# HoverPuck.net
KiCad netlist of a schematic drawn in EAGLE
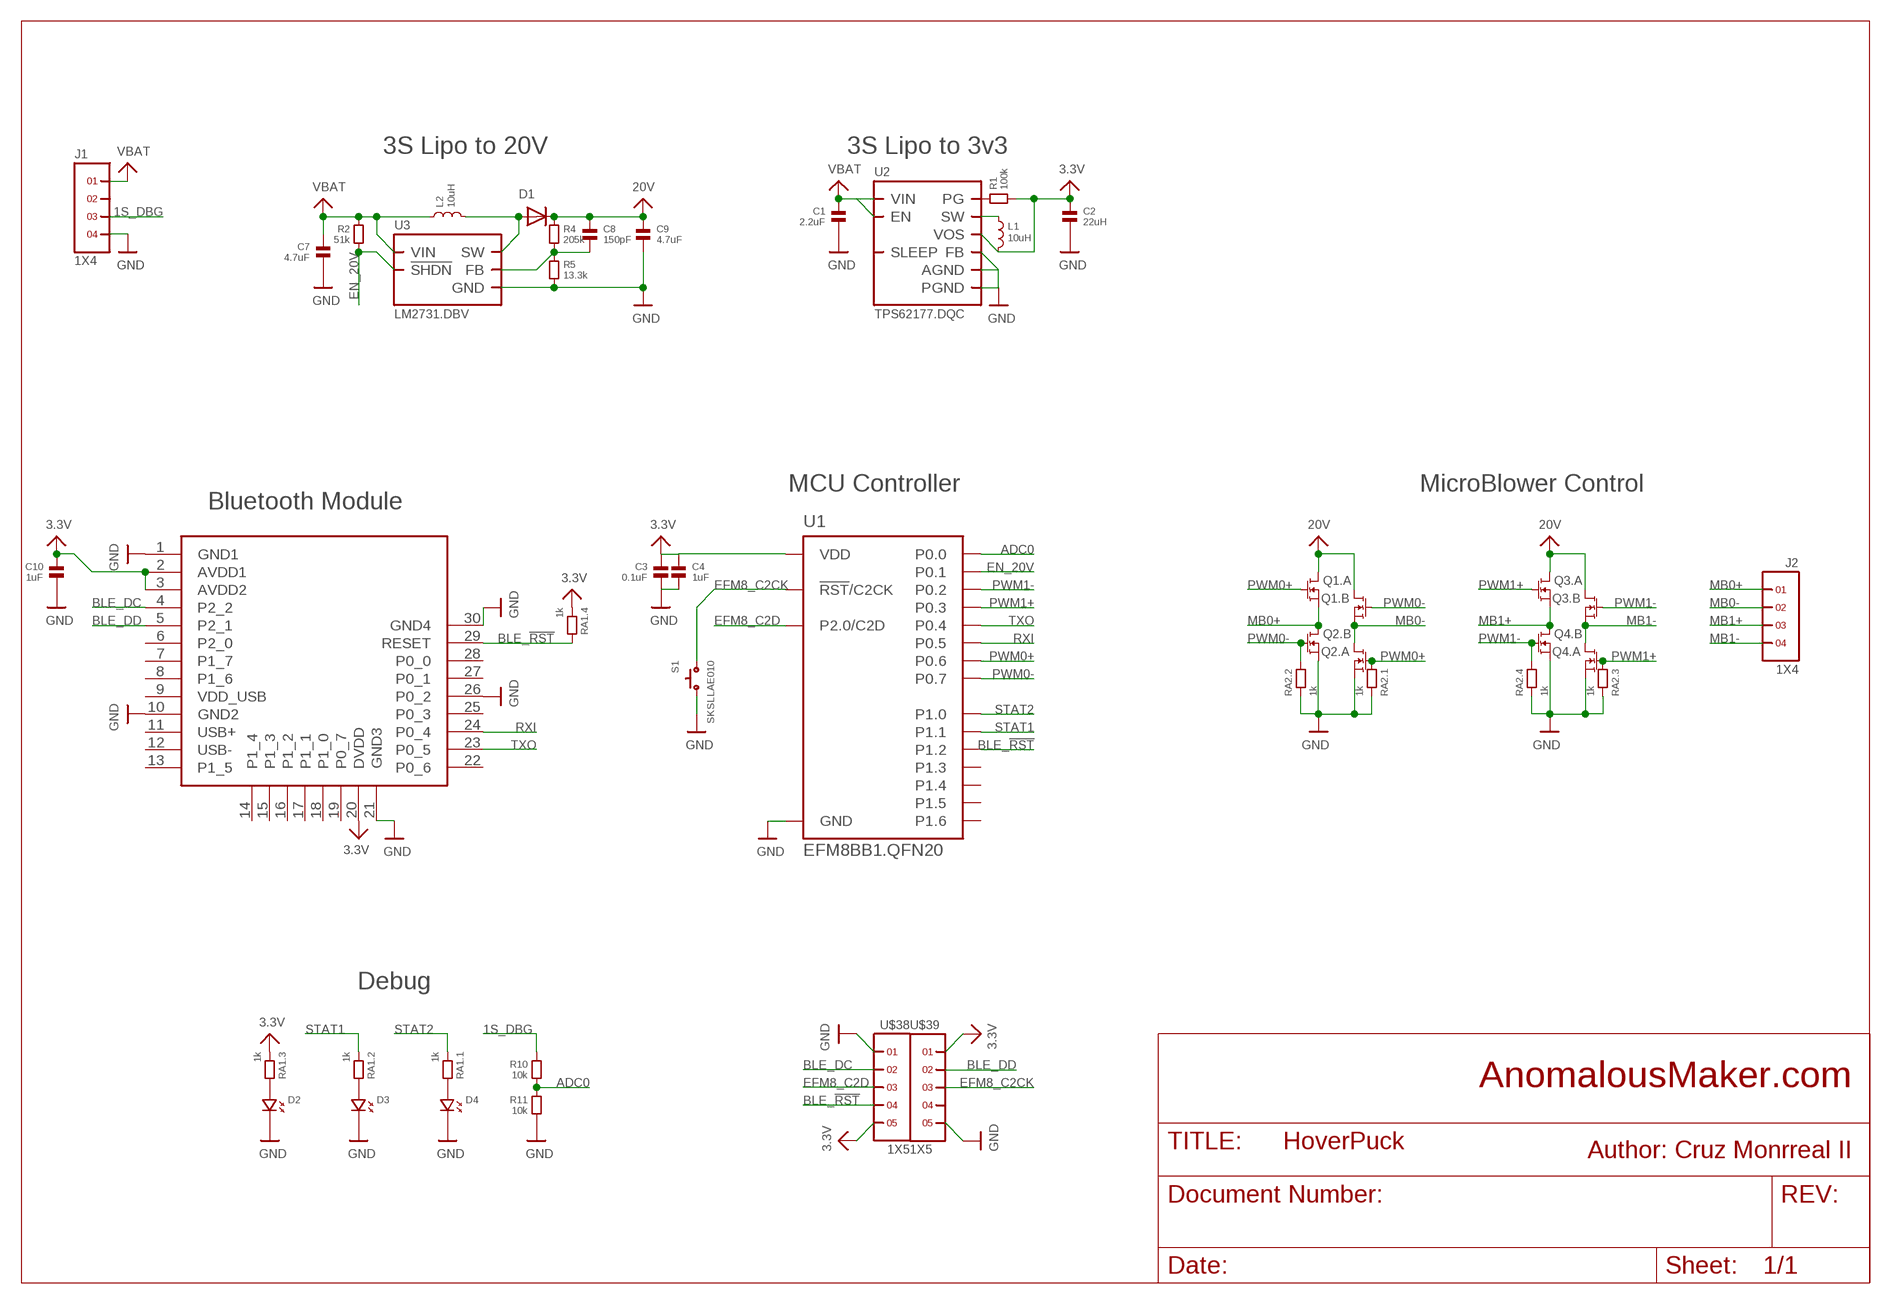
[diagram p0: schematic, sheet 1]

(export (version "E")
  (design (tool "Eeschema 10.0.6"))
  (components
    (comp (ref "C1")
      (value "2.2uF")
      (footprint "eagle-import:0603")
      (libsource (lib "eagle-import") (part "CAPACITOR.0603"))
    )
    (comp (ref "C2")
      (value "22uH")
      (footprint "eagle-import:0805")
      (libsource (lib "eagle-import") (part "CAPACITOR.0805"))
    )
    (comp (ref "C3")
      (value "0.1uF")
      (footprint "eagle-import:0603")
      (libsource (lib "eagle-import") (part "CAPACITOR.0603"))
    )
    (comp (ref "C4")
      (value "1uF")
      (footprint "eagle-import:0603")
      (libsource (lib "eagle-import") (part "CAPACITOR.0603"))
    )
    (comp (ref "C7")
      (value "4.7uF")
      (footprint "eagle-import:0805")
      (libsource (lib "eagle-import") (part "CAPACITOR.0805"))
    )
    (comp (ref "C8")
      (value "150pF")
      (footprint "eagle-import:0603")
      (libsource (lib "eagle-import") (part "CAPACITOR.0603"))
    )
    (comp (ref "C9")
      (value "4.7uF")
      (footprint "eagle-import:0805")
      (libsource (lib "eagle-import") (part "CAPACITOR.0805"))
    )
    (comp (ref "C10")
      (value "1uF")
      (footprint "eagle-import:0603")
      (libsource (lib "eagle-import") (part "CAPACITOR.0603"))
    )
    (comp (ref "D1")
      (value "MBR0530T1G")
      (footprint "eagle-import:SOD-123")
      (libsource (lib "eagle-import") (part "DIODESOD-123"))
    )
    (comp (ref "D2")
      (value "LED.0603")
      (footprint "eagle-import:0603.LED")
      (libsource (lib "eagle-import") (part "LED.0603"))
    )
    (comp (ref "D3")
      (value "LED.0603")
      (footprint "eagle-import:0603.LED")
      (libsource (lib "eagle-import") (part "LED.0603"))
    )
    (comp (ref "D4")
      (value "LED.0603")
      (footprint "eagle-import:0603.LED")
      (libsource (lib "eagle-import") (part "LED.0603"))
    )
    (comp (ref "J1")
      (value "1X4")
      (footprint "eagle-import:1X4")
      (libsource (lib "eagle-import") (part "1X4"))
    )
    (comp (ref "J2")
      (value "1X4")
      (footprint "eagle-import:1X4")
      (libsource (lib "eagle-import") (part "1X4"))
    )
    (comp (ref "L1")
      (value "10uH")
      (footprint "eagle-import:LPS4018")
      (libsource (lib "eagle-import") (part "INDUCTOR.LPS4018"))
    )
    (comp (ref "L2")
      (value "10uH")
      (footprint "eagle-import:SRN6045")
      (libsource (lib "eagle-import") (part "INDUCTOR-SRN6045"))
    )
    (comp (ref "Q1")
      (value "FDMA")
      (footprint "eagle-import:MICROFET.2X2")
      (libsource (lib "eagle-import") (part "FDMA"))
    )
    (comp (ref "Q2")
      (value "FDMA")
      (footprint "eagle-import:MICROFET.2X2")
      (libsource (lib "eagle-import") (part "FDMA"))
    )
    (comp (ref "Q3")
      (value "FDMA")
      (footprint "eagle-import:MICROFET.2X2")
      (libsource (lib "eagle-import") (part "FDMA"))
    )
    (comp (ref "Q4")
      (value "FDMA")
      (footprint "eagle-import:MICROFET.2X2")
      (libsource (lib "eagle-import") (part "FDMA"))
    )
    (comp (ref "R1")
      (value "100k")
      (footprint "eagle-import:0603")
      (libsource (lib "eagle-import") (part "RESISTOR.0603"))
    )
    (comp (ref "R2")
      (value "51k")
      (footprint "eagle-import:0603")
      (libsource (lib "eagle-import") (part "RESISTOR.0603"))
    )
    (comp (ref "R4")
      (value "205k")
      (footprint "eagle-import:0603")
      (libsource (lib "eagle-import") (part "RESISTOR.0603"))
    )
    (comp (ref "R5")
      (value "13.3k")
      (footprint "eagle-import:0603")
      (libsource (lib "eagle-import") (part "RESISTOR.0603"))
    )
    (comp (ref "R10")
      (value "10k")
      (footprint "eagle-import:0603")
      (libsource (lib "eagle-import") (part "RESISTOR.0603"))
    )
    (comp (ref "R11")
      (value "10k")
      (footprint "eagle-import:0603")
      (libsource (lib "eagle-import") (part "RESISTOR.0603"))
    )
    (comp (ref "RA1")
      (value "1k")
      (footprint "eagle-import:0603.4.C")
      (libsource (lib "eagle-import") (part "RA-4.0603"))
    )
    (comp (ref "RA2")
      (value "1k")
      (footprint "eagle-import:0603.4.C")
      (libsource (lib "eagle-import") (part "RA-4.0603"))
    )
    (comp (ref "S1")
      (value "SKSLLAE010")
      (footprint "eagle-import:SKSLLAE010")
      (libsource (lib "eagle-import") (part "SKSLLAE010"))
    )
    (comp (ref "U$38")
      (value "1X5")
      (footprint "eagle-import:1X5")
      (libsource (lib "eagle-import") (part "1X5"))
    )
    (comp (ref "U$39")
      (value "1X5")
      (footprint "eagle-import:1X5")
      (libsource (lib "eagle-import") (part "1X5"))
    )
    (comp (ref "U1")
      (value "EFM8BB1.QFN20")
      (footprint "eagle-import:QFN20")
      (libsource (lib "eagle-import") (part "EFM8BB1.QFN20"))
    )
    (comp (ref "U2")
      (value "TPS62177.DQC")
      (footprint "eagle-import:DQC")
      (libsource (lib "eagle-import") (part "TPS62177.DQC"))
    )
    (comp (ref "U3")
      (value "LM2731.DBV")
      (footprint "eagle-import:DBV.5")
      (libsource (lib "eagle-import") (part "LM2731.DBV"))
    )
    (comp (ref "U4")
      (value "BLE112-A")
      (footprint "eagle-import:BLE112-A")
      (libsource (lib "eagle-import") (part "BLE112-A"))
    )
  )
  (nets
    (net (code "1") (name "/1S_DBG") (class "Default")
      (node (ref "J1") (pin "3") (pinfunction "3_3") (pintype "bidirectional"))
      (node (ref "R10") (pin "1") (pinfunction "1_1") (pintype "bidirectional"))
    )
    (net (code "2") (name "/ADC0") (class "Default")
      (node (ref "R10") (pin "2") (pinfunction "2_2") (pintype "bidirectional"))
      (node (ref "R11") (pin "1") (pinfunction "1_1") (pintype "bidirectional"))
      (node (ref "U1") (pin "2") (pinfunction "P0.0_2") (pintype "bidirectional"))
    )
    (net (code "3") (name "/BLE_DC") (class "Default")
      (node (ref "U$38") (pin "2") (pinfunction "2_2") (pintype "bidirectional"))
      (node (ref "U4") (pin "4") (pinfunction "P2_2_4") (pintype "bidirectional"))
    )
    (net (code "4") (name "/BLE_DD") (class "Default")
      (node (ref "U$39") (pin "2") (pinfunction "2_2") (pintype "bidirectional"))
      (node (ref "U4") (pin "5") (pinfunction "P2_1_5") (pintype "bidirectional"))
    )
    (net (code "5") (name "/BLE_~{RST}") (class "Default")
      (node (ref "RA1") (pin "8") (pinfunction "2_8") (pintype "bidirectional"))
      (node (ref "U$38") (pin "4") (pinfunction "4_4") (pintype "bidirectional"))
      (node (ref "U1") (pin "11") (pinfunction "P1.2_11") (pintype "bidirectional"))
      (node (ref "U4") (pin "29") (pinfunction "RESET_29") (pintype "bidirectional"))
    )
    (net (code "6") (name "/EFM8_C2CK") (class "Default")
      (node (ref "S1") (pin "1") (pinfunction "1_1") (pintype "bidirectional"))
      (node (ref "U$39") (pin "3") (pinfunction "3_3") (pintype "bidirectional"))
      (node (ref "U1") (pin "5") (pinfunction "~{RST}/C2CK_5") (pintype "input"))
    )
    (net (code "7") (name "/EFM8_C2D") (class "Default")
      (node (ref "U$38") (pin "3") (pinfunction "3_3") (pintype "bidirectional"))
      (node (ref "U1") (pin "6") (pinfunction "P2.0/C2D_6") (pintype "bidirectional"))
    )
    (net (code "8") (name "/EN_20V") (class "Default")
      (node (ref "R2") (pin "2") (pinfunction "2_2") (pintype "bidirectional"))
      (node (ref "U1") (pin "1") (pinfunction "P0.1_1") (pintype "bidirectional"))
      (node (ref "U3") (pin "4") (pinfunction "~{SHDN}_4") (pintype "bidirectional"))
    )
    (net (code "9") (name "/MB0+") (class "Default")
      (node (ref "J2") (pin "1") (pinfunction "1_1") (pintype "bidirectional"))
      (node (ref "Q1") (pin "1") (pinfunction "S_1") (pintype "bidirectional"))
      (node (ref "Q2") (pin "3") (pinfunction "D_3") (pintype "bidirectional"))
      (node (ref "Q2") (pin "PAD@2") (pinfunction "D_PAD@2") (pintype "bidirectional"))
    )
    (net (code "10") (name "/MB0-") (class "Default")
      (node (ref "J2") (pin "2") (pinfunction "2_2") (pintype "bidirectional"))
      (node (ref "Q1") (pin "4") (pinfunction "S_4") (pintype "bidirectional"))
      (node (ref "Q2") (pin "6") (pinfunction "D_6") (pintype "bidirectional"))
      (node (ref "Q2") (pin "PAD@1") (pinfunction "D_PAD@1") (pintype "bidirectional"))
    )
    (net (code "11") (name "/MB1+") (class "Default")
      (node (ref "J2") (pin "3") (pinfunction "3_3") (pintype "bidirectional"))
      (node (ref "Q3") (pin "1") (pinfunction "S_1") (pintype "bidirectional"))
      (node (ref "Q4") (pin "3") (pinfunction "D_3") (pintype "bidirectional"))
      (node (ref "Q4") (pin "PAD@2") (pinfunction "D_PAD@2") (pintype "bidirectional"))
    )
    (net (code "12") (name "/MB1-") (class "Default")
      (node (ref "J2") (pin "4") (pinfunction "4_4") (pintype "bidirectional"))
      (node (ref "Q3") (pin "4") (pinfunction "S_4") (pintype "bidirectional"))
      (node (ref "Q4") (pin "6") (pinfunction "D_6") (pintype "bidirectional"))
      (node (ref "Q4") (pin "PAD@1") (pinfunction "D_PAD@1") (pintype "bidirectional"))
    )
    (net (code "13") (name "/PWM0+") (class "Default")
      (node (ref "Q1") (pin "2") (pinfunction "G_2") (pintype "bidirectional"))
      (node (ref "Q2") (pin "2") (pinfunction "G_2") (pintype "bidirectional"))
      (node (ref "RA2") (pin "2") (pinfunction "2_2") (pintype "bidirectional"))
      (node (ref "U1") (pin "16") (pinfunction "P0.6_16") (pintype "bidirectional"))
    )
    (net (code "14") (name "/PWM0-") (class "Default")
      (node (ref "Q1") (pin "5") (pinfunction "G_5") (pintype "bidirectional"))
      (node (ref "Q2") (pin "5") (pinfunction "G_5") (pintype "bidirectional"))
      (node (ref "RA2") (pin "4") (pinfunction "2_4") (pintype "bidirectional"))
      (node (ref "U1") (pin "15") (pinfunction "P0.7_15") (pintype "bidirectional"))
    )
    (net (code "15") (name "/PWM1+") (class "Default")
      (node (ref "Q3") (pin "2") (pinfunction "G_2") (pintype "bidirectional"))
      (node (ref "Q4") (pin "2") (pinfunction "G_2") (pintype "bidirectional"))
      (node (ref "RA2") (pin "6") (pinfunction "2_6") (pintype "bidirectional"))
      (node (ref "U1") (pin "19") (pinfunction "P0.3_19") (pintype "bidirectional"))
    )
    (net (code "16") (name "/PWM1-") (class "Default")
      (node (ref "Q3") (pin "5") (pinfunction "G_5") (pintype "bidirectional"))
      (node (ref "Q4") (pin "5") (pinfunction "G_5") (pintype "bidirectional"))
      (node (ref "RA2") (pin "8") (pinfunction "2_8") (pintype "bidirectional"))
      (node (ref "U1") (pin "20") (pinfunction "P0.2_20") (pintype "bidirectional"))
    )
    (net (code "17") (name "/RXI") (class "Default")
      (node (ref "U1") (pin "17") (pinfunction "P0.5_17") (pintype "bidirectional"))
      (node (ref "U4") (pin "24") (pinfunction "P0_4_24") (pintype "bidirectional"))
    )
    (net (code "18") (name "/STAT1") (class "Default")
      (node (ref "RA1") (pin "3") (pinfunction "1_3") (pintype "bidirectional"))
      (node (ref "U1") (pin "13") (pinfunction "P1.1_13") (pintype "bidirectional"))
    )
    (net (code "19") (name "/STAT2") (class "Default")
      (node (ref "RA1") (pin "1") (pinfunction "1_1") (pintype "bidirectional"))
      (node (ref "U1") (pin "14") (pinfunction "P1.0_14") (pintype "bidirectional"))
    )
    (net (code "20") (name "/TXO") (class "Default")
      (node (ref "U1") (pin "18") (pinfunction "P0.4_18") (pintype "bidirectional"))
      (node (ref "U4") (pin "23") (pinfunction "P0_5_23") (pintype "bidirectional"))
    )
    (net (code "21") (name "3.3V") (class "Default")
      (node (ref "C10") (pin "1") (pinfunction "1_1") (pintype "bidirectional"))
      (node (ref "C2") (pin "1") (pinfunction "1_1") (pintype "bidirectional"))
      (node (ref "C3") (pin "1") (pinfunction "1_1") (pintype "bidirectional"))
      (node (ref "C4") (pin "1") (pinfunction "1_1") (pintype "bidirectional"))
      (node (ref "L1") (pin "2") (pinfunction "2_2") (pintype "passive"))
      (node (ref "R1") (pin "2") (pinfunction "2_2") (pintype "bidirectional"))
      (node (ref "RA1") (pin "5") (pinfunction "1_5") (pintype "bidirectional"))
      (node (ref "RA1") (pin "7") (pinfunction "1_7") (pintype "bidirectional"))
      (node (ref "U$38") (pin "5") (pinfunction "5_5") (pintype "bidirectional"))
      (node (ref "U$39") (pin "1") (pinfunction "1_1") (pintype "bidirectional"))
      (node (ref "U1") (pin "4") (pinfunction "VDD_4") (pintype "power_in"))
      (node (ref "U2") (pin "10") (pinfunction "VOS_10") (pintype "bidirectional"))
      (node (ref "U4") (pin "2") (pinfunction "AVDD1_2") (pintype "bidirectional"))
      (node (ref "U4") (pin "20") (pinfunction "DVDD_20") (pintype "bidirectional"))
      (node (ref "U4") (pin "3") (pinfunction "AVDD2_3") (pintype "bidirectional"))
    )
    (net (code "22") (name "20V") (class "Default")
      (node (ref "C8") (pin "1") (pinfunction "1_1") (pintype "bidirectional"))
      (node (ref "C9") (pin "1") (pinfunction "1_1") (pintype "bidirectional"))
      (node (ref "D1") (pin "C") (pinfunction "C_C") (pintype "passive"))
      (node (ref "Q1") (pin "3") (pinfunction "D_3") (pintype "bidirectional"))
      (node (ref "Q1") (pin "6") (pinfunction "D_6") (pintype "bidirectional"))
      (node (ref "Q1") (pin "PAD@1") (pinfunction "D_PAD@1") (pintype "bidirectional"))
      (node (ref "Q1") (pin "PAD@2") (pinfunction "D_PAD@2") (pintype "bidirectional"))
      (node (ref "Q3") (pin "3") (pinfunction "D_3") (pintype "bidirectional"))
      (node (ref "Q3") (pin "6") (pinfunction "D_6") (pintype "bidirectional"))
      (node (ref "Q3") (pin "PAD@1") (pinfunction "D_PAD@1") (pintype "bidirectional"))
      (node (ref "Q3") (pin "PAD@2") (pinfunction "D_PAD@2") (pintype "bidirectional"))
      (node (ref "R4") (pin "1") (pinfunction "1_1") (pintype "bidirectional"))
    )
    (net (code "23") (name "GND") (class "Default")
      (node (ref "C1") (pin "2") (pinfunction "2_2") (pintype "bidirectional"))
      (node (ref "C10") (pin "2") (pinfunction "2_2") (pintype "bidirectional"))
      (node (ref "C2") (pin "2") (pinfunction "2_2") (pintype "bidirectional"))
      (node (ref "C3") (pin "2") (pinfunction "2_2") (pintype "bidirectional"))
      (node (ref "C4") (pin "2") (pinfunction "2_2") (pintype "bidirectional"))
      (node (ref "C7") (pin "2") (pinfunction "2_2") (pintype "bidirectional"))
      (node (ref "C9") (pin "2") (pinfunction "2_2") (pintype "bidirectional"))
      (node (ref "D2") (pin "P$2") (pinfunction "2_P$2") (pintype "bidirectional"))
      (node (ref "D3") (pin "P$2") (pinfunction "2_P$2") (pintype "bidirectional"))
      (node (ref "D4") (pin "P$2") (pinfunction "2_P$2") (pintype "bidirectional"))
      (node (ref "J1") (pin "4") (pinfunction "4_4") (pintype "bidirectional"))
      (node (ref "Q2") (pin "1") (pinfunction "S_1") (pintype "bidirectional"))
      (node (ref "Q2") (pin "4") (pinfunction "S_4") (pintype "bidirectional"))
      (node (ref "Q4") (pin "1") (pinfunction "S_1") (pintype "bidirectional"))
      (node (ref "Q4") (pin "4") (pinfunction "S_4") (pintype "bidirectional"))
      (node (ref "R11") (pin "2") (pinfunction "2_2") (pintype "bidirectional"))
      (node (ref "R5") (pin "2") (pinfunction "2_2") (pintype "bidirectional"))
      (node (ref "RA2") (pin "1") (pinfunction "1_1") (pintype "bidirectional"))
      (node (ref "RA2") (pin "3") (pinfunction "1_3") (pintype "bidirectional"))
      (node (ref "RA2") (pin "5") (pinfunction "1_5") (pintype "bidirectional"))
      (node (ref "RA2") (pin "7") (pinfunction "1_7") (pintype "bidirectional"))
      (node (ref "S1") (pin "2") (pinfunction "2_2") (pintype "bidirectional"))
      (node (ref "U$38") (pin "1") (pinfunction "1_1") (pintype "bidirectional"))
      (node (ref "U$39") (pin "5") (pinfunction "5_5") (pintype "bidirectional"))
      (node (ref "U1") (pin "12") (pinfunction "GND_12") (pintype "power_in"))
      (node (ref "U1") (pin "3") (pinfunction "GND_3") (pintype "power_in"))
      (node (ref "U1") (pin "PAD") (pinfunction "GND_PAD") (pintype "power_in"))
      (node (ref "U2") (pin "1") (pinfunction "PGND_1") (pintype "bidirectional"))
      (node (ref "U2") (pin "5") (pinfunction "FB_5") (pintype "bidirectional"))
      (node (ref "U2") (pin "6") (pinfunction "AGND_6") (pintype "bidirectional"))
      (node (ref "U2") (pin "PAD") (pinfunction "PGND_PAD") (pintype "bidirectional"))
      (node (ref "U3") (pin "2") (pinfunction "GND_2") (pintype "bidirectional"))
      (node (ref "U4") (pin "1") (pinfunction "GND1_1") (pintype "bidirectional"))
      (node (ref "U4") (pin "10") (pinfunction "GND2_10") (pintype "bidirectional"))
      (node (ref "U4") (pin "21") (pinfunction "GND3_21") (pintype "bidirectional"))
      (node (ref "U4") (pin "26") (pinfunction "P0_2_26") (pintype "bidirectional"))
      (node (ref "U4") (pin "30") (pinfunction "GND4_30") (pintype "bidirectional"))
    )
    (net (code "24") (name "Net-(D2-1)") (class "Default")
      (node (ref "D2") (pin "P$1") (pinfunction "1_P$1") (pintype "bidirectional"))
      (node (ref "RA1") (pin "6") (pinfunction "2_6") (pintype "bidirectional"))
    )
    (net (code "25") (name "Net-(D3-1)") (class "Default")
      (node (ref "D3") (pin "P$1") (pinfunction "1_P$1") (pintype "bidirectional"))
      (node (ref "RA1") (pin "4") (pinfunction "2_4") (pintype "bidirectional"))
    )
    (net (code "26") (name "Net-(D4-1)") (class "Default")
      (node (ref "D4") (pin "P$1") (pinfunction "1_P$1") (pintype "bidirectional"))
      (node (ref "RA1") (pin "2") (pinfunction "2_2") (pintype "bidirectional"))
    )
    (net (code "27") (name "Net-(U2-PG)") (class "Default")
      (node (ref "R1") (pin "1") (pinfunction "1_1") (pintype "bidirectional"))
      (node (ref "U2") (pin "7") (pinfunction "PG_7") (pintype "bidirectional"))
    )
    (net (code "28") (name "Net-(U2-SW)") (class "Default")
      (node (ref "L1") (pin "1") (pinfunction "1_1") (pintype "passive"))
      (node (ref "U2") (pin "9") (pinfunction "SW_9") (pintype "bidirectional"))
    )
    (net (code "29") (name "Net-(U3-FB)") (class "Default")
      (node (ref "C8") (pin "2") (pinfunction "2_2") (pintype "bidirectional"))
      (node (ref "R4") (pin "2") (pinfunction "2_2") (pintype "bidirectional"))
      (node (ref "R5") (pin "1") (pinfunction "1_1") (pintype "bidirectional"))
      (node (ref "U3") (pin "3") (pinfunction "FB_3") (pintype "bidirectional"))
    )
    (net (code "30") (name "Net-(U3-SW)") (class "Default")
      (node (ref "D1") (pin "A") (pinfunction "A_A") (pintype "passive"))
      (node (ref "L2") (pin "2") (pinfunction "2_2") (pintype "passive"))
      (node (ref "U3") (pin "1") (pinfunction "SW_1") (pintype "bidirectional"))
    )
    (net (code "31") (name "VBAT") (class "Default")
      (node (ref "C1") (pin "1") (pinfunction "1_1") (pintype "bidirectional"))
      (node (ref "C7") (pin "1") (pinfunction "1_1") (pintype "bidirectional"))
      (node (ref "J1") (pin "1") (pinfunction "1_1") (pintype "bidirectional"))
      (node (ref "L2") (pin "1") (pinfunction "1_1") (pintype "passive"))
      (node (ref "R2") (pin "1") (pinfunction "1_1") (pintype "bidirectional"))
      (node (ref "U2") (pin "2") (pinfunction "VIN_2") (pintype "bidirectional"))
      (node (ref "U2") (pin "3") (pinfunction "EN_3") (pintype "bidirectional"))
      (node (ref "U3") (pin "5") (pinfunction "VIN_5") (pintype "bidirectional"))
    )
    (net (code "32") (name "unconnected-(J1-Pad2)") (class "Default")
      (node (ref "J1") (pin "2") (pinfunction "2_2") (pintype "bidirectional"))
    )
    (net (code "33") (name "unconnected-(U$39-Pad4)") (class "Default")
      (node (ref "U$39") (pin "4") (pinfunction "4_4") (pintype "bidirectional"))
    )
    (net (code "34") (name "unconnected-(U1-P1.3-Pad10)") (class "Default")
      (node (ref "U1") (pin "10") (pinfunction "P1.3_10") (pintype "bidirectional"))
    )
    (net (code "35") (name "unconnected-(U1-P1.4-Pad9)") (class "Default")
      (node (ref "U1") (pin "9") (pinfunction "P1.4_9") (pintype "bidirectional"))
    )
    (net (code "36") (name "unconnected-(U1-P1.5-Pad8)") (class "Default")
      (node (ref "U1") (pin "8") (pinfunction "P1.5_8") (pintype "bidirectional"))
    )
    (net (code "37") (name "unconnected-(U1-P1.6-Pad7)") (class "Default")
      (node (ref "U1") (pin "7") (pinfunction "P1.6_7") (pintype "bidirectional"))
    )
    (net (code "38") (name "unconnected-(U2-SLEEP-Pad8)") (class "Default")
      (node (ref "U2") (pin "8") (pinfunction "SLEEP_8") (pintype "bidirectional"))
    )
    (net (code "39") (name "unconnected-(U4-P0_0-Pad28)") (class "Default")
      (node (ref "U4") (pin "28") (pinfunction "P0_0_28") (pintype "bidirectional"))
    )
    (net (code "40") (name "unconnected-(U4-P0_1-Pad27)") (class "Default")
      (node (ref "U4") (pin "27") (pinfunction "P0_1_27") (pintype "bidirectional"))
    )
    (net (code "41") (name "unconnected-(U4-P0_3-Pad25)") (class "Default")
      (node (ref "U4") (pin "25") (pinfunction "P0_3_25") (pintype "bidirectional"))
    )
    (net (code "42") (name "unconnected-(U4-P0_6-Pad22)") (class "Default")
      (node (ref "U4") (pin "22") (pinfunction "P0_6_22") (pintype "bidirectional"))
    )
    (net (code "43") (name "unconnected-(U4-P0_7-Pad19)") (class "Default")
      (node (ref "U4") (pin "19") (pinfunction "P0_7_19") (pintype "bidirectional"))
    )
    (net (code "44") (name "unconnected-(U4-P1_0-Pad18)") (class "Default")
      (node (ref "U4") (pin "18") (pinfunction "P1_0_18") (pintype "bidirectional"))
    )
    (net (code "45") (name "unconnected-(U4-P1_1-Pad17)") (class "Default")
      (node (ref "U4") (pin "17") (pinfunction "P1_1_17") (pintype "bidirectional"))
    )
    (net (code "46") (name "unconnected-(U4-P1_2-Pad16)") (class "Default")
      (node (ref "U4") (pin "16") (pinfunction "P1_2_16") (pintype "bidirectional"))
    )
    (net (code "47") (name "unconnected-(U4-P1_3-Pad15)") (class "Default")
      (node (ref "U4") (pin "15") (pinfunction "P1_3_15") (pintype "bidirectional"))
    )
    (net (code "48") (name "unconnected-(U4-P1_4-Pad14)") (class "Default")
      (node (ref "U4") (pin "14") (pinfunction "P1_4_14") (pintype "bidirectional"))
    )
    (net (code "49") (name "unconnected-(U4-P1_5-Pad13)") (class "Default")
      (node (ref "U4") (pin "13") (pinfunction "P1_5_13") (pintype "bidirectional"))
    )
    (net (code "50") (name "unconnected-(U4-P1_6-Pad8)") (class "Default")
      (node (ref "U4") (pin "8") (pinfunction "P1_6_8") (pintype "bidirectional"))
    )
    (net (code "51") (name "unconnected-(U4-P1_7-Pad7)") (class "Default")
      (node (ref "U4") (pin "7") (pinfunction "P1_7_7") (pintype "bidirectional"))
    )
    (net (code "52") (name "unconnected-(U4-P2_0-Pad6)") (class "Default")
      (node (ref "U4") (pin "6") (pinfunction "P2_0_6") (pintype "bidirectional"))
    )
    (net (code "53") (name "unconnected-(U4-USB+-Pad11)") (class "Default")
      (node (ref "U4") (pin "11") (pinfunction "USB+_11") (pintype "bidirectional"))
    )
    (net (code "54") (name "unconnected-(U4-USB--Pad12)") (class "Default")
      (node (ref "U4") (pin "12") (pinfunction "USB-_12") (pintype "bidirectional"))
    )
    (net (code "55") (name "unconnected-(U4-VDD_USB-Pad9)") (class "Default")
      (node (ref "U4") (pin "9") (pinfunction "VDD_USB_9") (pintype "bidirectional"))
    )
  )
)
